# heater_control.net
KiCad netlist of a schematic drawn in Altium Designer
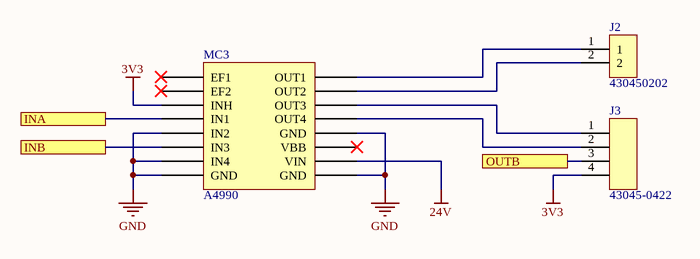
[diagram p0: heater_control.SchDoc]

(export (version "E")
  (design (tool "Eeschema 10.0.6"))
  (components
    (comp (ref "J2")
      (value "__Template_Connector_1X2")
      (footprint "MOLEX_430450202")
      (description "CONN, HDR, R/A, 2x1, 3MM P, 7.37MM H, GOLD, TH")
      (fields (field (name "MFG") "Molex, LLC") (field (name "MFG P/N") "430450202"))
      (libsource (lib "AltiumReleaseLibDB") (part "__Template_Connector_1X2"))
    )
    (comp (ref "J3")
      (value "CONN_MOLEX_MICROFIT_DOUBLE_ROW_RA_TH_4POS_LOCK")
      (footprint "MOLEX_MICROFIT_DOUBLE_ROW_RA_TH_4POS_43045-0422")
      (description "CONN MOLEX MICROFIT 4POS RA GOLD")
      (fields (field (name "MFG") "Molex Inc") (field (name "MFG P/N") "43045-0422"))
      (libsource (lib "AltiumReleaseLibDB") (part "CONN_MOLEX_MICROFIT_DOUBLE_ROW_RA_TH_4POS_LOCK"))
    )
    (comp (ref "MC3")
      (value "A4990")
      (footprint "A4990 Dual Motor Driver Carrier")
      (libsource (lib "brew_lib") (part "A4990 Dual Motor Driver Carrier"))
    )
  )
  (nets
    (net (code "1") (name "/INA") (class "Default")
      (node (ref "MC3") (pin "4") (pinfunction "IN1_4") (pintype "passive"))
    )
    (net (code "2") (name "/INB") (class "Default")
      (node (ref "MC3") (pin "6") (pinfunction "IN3_6") (pintype "passive"))
    )
    (net (code "3") (name "/OUTB") (class "Default")
      (node (ref "J3") (pin "3") (pinfunction "3_3") (pintype "passive"))
    )
    (net (code "4") (name "3V3") (class "Default")
      (node (ref "J3") (pin "4") (pinfunction "4_4") (pintype "passive"))
      (node (ref "MC3") (pin "3") (pinfunction "INH_3") (pintype "passive"))
    )
    (net (code "5") (name "24V") (class "Default")
      (node (ref "MC3") (pin "10") (pinfunction "VIN_10") (pintype "passive"))
    )
    (net (code "6") (name "GND") (class "Default")
      (node (ref "MC3") (pin "12") (pinfunction "GND_12") (pintype "passive"))
      (node (ref "MC3") (pin "5") (pinfunction "IN2_5") (pintype "passive"))
      (node (ref "MC3") (pin "7") (pinfunction "IN4_7") (pintype "passive"))
      (node (ref "MC3") (pin "8") (pinfunction "GND_8") (pintype "passive"))
      (node (ref "MC3") (pin "9") (pinfunction "GND_9") (pintype "passive"))
    )
    (net (code "7") (name "Net-(MC3-OUT1)") (class "Default")
      (node (ref "J2") (pin "1") (pinfunction "1_1") (pintype "passive"))
      (node (ref "MC3") (pin "16") (pinfunction "OUT1_16") (pintype "passive"))
    )
    (net (code "8") (name "Net-(MC3-OUT2)") (class "Default")
      (node (ref "J2") (pin "2") (pinfunction "2_2") (pintype "passive"))
      (node (ref "MC3") (pin "15") (pinfunction "OUT2_15") (pintype "passive"))
    )
    (net (code "9") (name "Net-(MC3-OUT3)") (class "Default")
      (node (ref "J3") (pin "1") (pinfunction "1_1") (pintype "passive"))
      (node (ref "MC3") (pin "14") (pinfunction "OUT3_14") (pintype "passive"))
    )
    (net (code "10") (name "Net-(MC3-OUT4)") (class "Default")
      (node (ref "J3") (pin "2") (pinfunction "2_2") (pintype "passive"))
      (node (ref "MC3") (pin "13") (pinfunction "OUT4_13") (pintype "passive"))
    )
    (net (code "11") (name "unconnected-(MC3-EF1-Pad1)") (class "Default")
      (node (ref "MC3") (pin "1") (pinfunction "EF1_1") (pintype "passive+no_connect"))
    )
    (net (code "12") (name "unconnected-(MC3-EF2-Pad2)") (class "Default")
      (node (ref "MC3") (pin "2") (pinfunction "EF2_2") (pintype "passive+no_connect"))
    )
    (net (code "13") (name "unconnected-(MC3-VBB-Pad11)") (class "Default")
      (node (ref "MC3") (pin "11") (pinfunction "VBB_11") (pintype "passive+no_connect"))
    )
  )
)
